# D1-Periph.net
KiCad netlist of a schematic drawn in Altium Designer
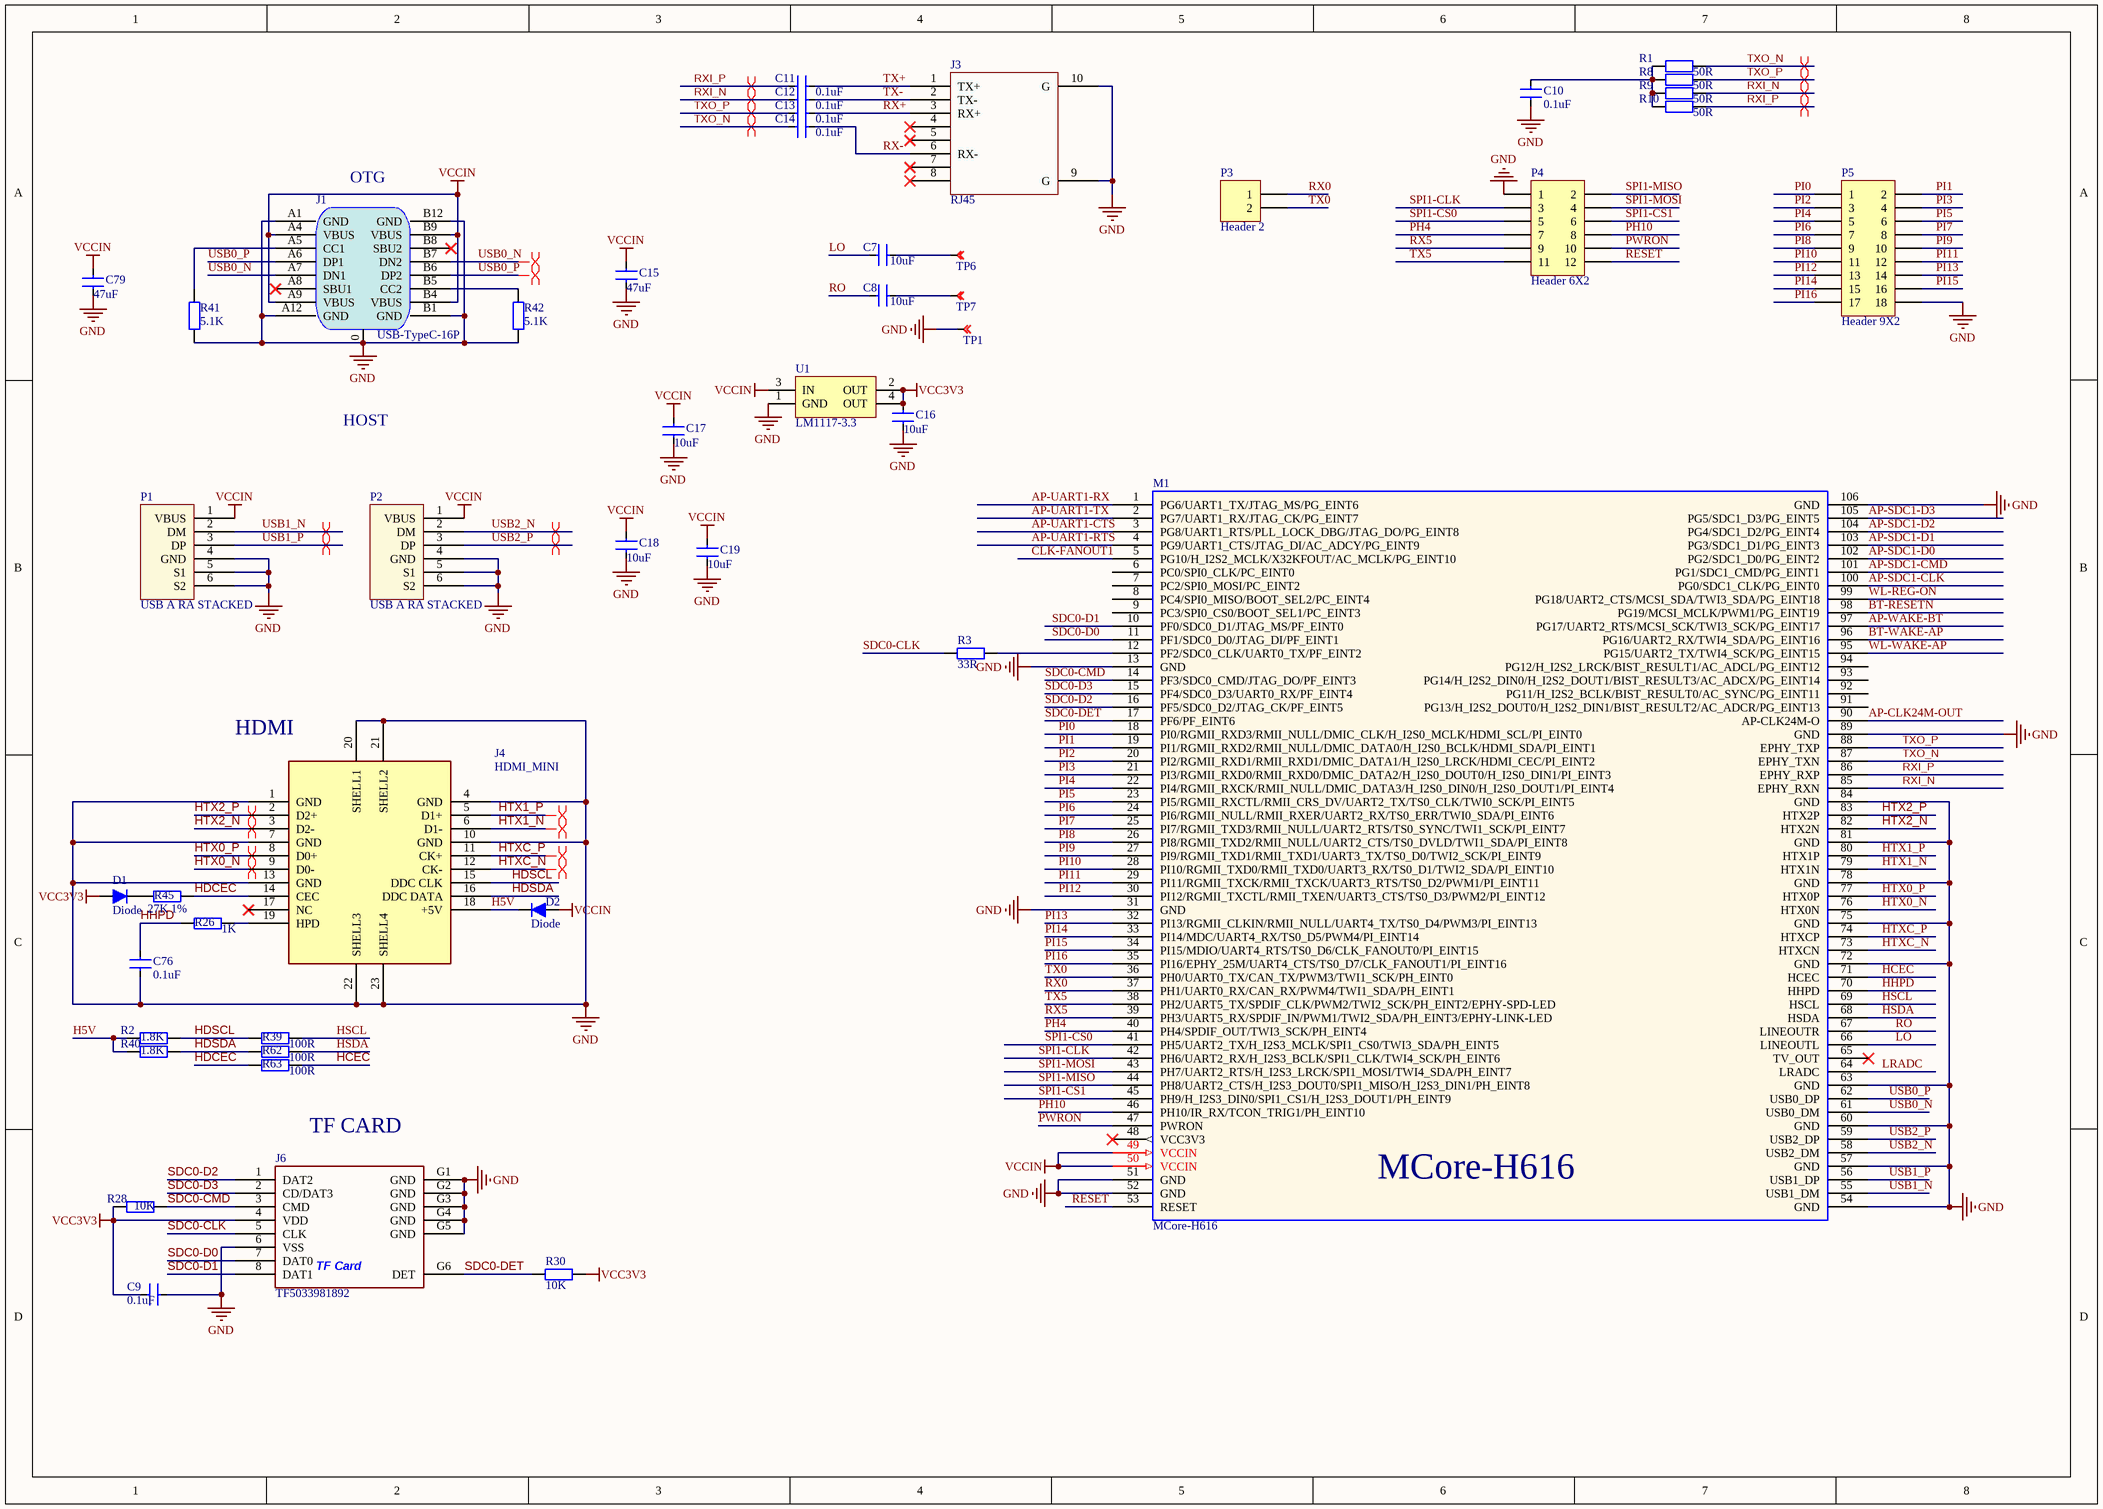
[diagram p0: D1-Periph.SchDoc]

(export (version "E")
  (design (tool "Eeschema 10.0.6"))
  (components
    (comp (ref "C7")
      (value "10uF")
      (footprint "C0402")
      (description "普通小电容")
      (libsource (lib "LIB_MANGO") (part "CAP"))
    )
    (comp (ref "C8")
      (value "10uF")
      (footprint "C0402")
      (description "普通小电容")
      (libsource (lib "LIB_MANGO") (part "CAP"))
    )
    (comp (ref "C9")
      (value "0.1uF")
      (footprint "C0402")
      (description "普通小电容")
      (libsource (lib "LIB_MANGO") (part "CAP"))
    )
    (comp (ref "C10")
      (value "0.1uF")
      (footprint "C0402")
      (description "普通小电容")
      (libsource (lib "LIB_MANGO") (part "CAP"))
    )
    (comp (ref "C11")
      (value "0.1uF")
      (footprint "C0402")
      (description "普通小电容")
      (libsource (lib "LIB_MANGO") (part "CAP"))
    )
    (comp (ref "C12")
      (value "0.1uF")
      (footprint "C0402")
      (description "普通小电容")
      (libsource (lib "LIB_MANGO") (part "CAP"))
    )
    (comp (ref "C13")
      (value "0.1uF")
      (footprint "C0402")
      (description "普通小电容")
      (libsource (lib "LIB_MANGO") (part "CAP"))
    )
    (comp (ref "C14")
      (value "0.1uF")
      (footprint "C0402")
      (description "普通小电容")
      (libsource (lib "LIB_MANGO") (part "CAP"))
    )
    (comp (ref "C15")
      (value "47uF")
      (footprint "C0603")
      (description "普通小电容")
      (libsource (lib "LIB_MANGO") (part "CAP"))
    )
    (comp (ref "C16")
      (value "10uF")
      (footprint "C0402")
      (description "普通小电容")
      (libsource (lib "LIB_MANGO") (part "CAP"))
    )
    (comp (ref "C17")
      (value "10uF")
      (footprint "C0402")
      (description "普通小电容")
      (libsource (lib "LIB_MANGO") (part "CAP"))
    )
    (comp (ref "C18")
      (value "10uF")
      (footprint "C0402")
      (description "普通小电容")
      (libsource (lib "LIB_MANGO") (part "CAP"))
    )
    (comp (ref "C19")
      (value "10uF")
      (footprint "C0402")
      (description "普通小电容")
      (libsource (lib "LIB_MANGO") (part "CAP"))
    )
    (comp (ref "C76")
      (value "0.1uF")
      (footprint "C0402")
      (description "普通小电容")
      (libsource (lib "LIB_MANGO") (part "CAP"))
    )
    (comp (ref "C79")
      (value "47uF")
      (footprint "C0603")
      (description "普通小电容")
      (libsource (lib "LIB_MANGO") (part "CAP"))
    )
    (comp (ref "D1")
      (value "Diode")
      (footprint "SOD523")
      (description "普通二极管")
      (libsource (lib "LIB_MANGO") (part "Diode"))
    )
    (comp (ref "D2")
      (value "Diode")
      (footprint "SOD523")
      (description "普通二极管")
      (libsource (lib "LIB_MANGO") (part "Diode"))
    )
    (comp (ref "J1")
      (value "USB-TypeC-16P")
      (footprint "usb-typec-16p")
      (libsource (lib "LIB_MANGO") (part "USB-TypeC-16P"))
    )
    (comp (ref "J3")
      (value "RJ45")
      (footprint "RJ45")
      (description "RJ45不带网络变压器")
      (libsource (lib "LIB_MANGO") (part "RJ45"))
    )
    (comp (ref "J4")
      (value "HDMI_MINI")
      (footprint "HDMI_T _mini")
      (libsource (lib "LIB_MANGO") (part "HDMI_MINI"))
    )
    (comp (ref "J6")
      (value "TF5033981892")
      (footprint "TFCARD-1040310811")
      (libsource (lib "LIB_MANGO") (part "TF5033981892"))
    )
    (comp (ref "M1")
      (value "MCore-H616")
      (footprint "MCore-H616")
      (libsource (lib "mcore-h616") (part "MCore-H616"))
    )
    (comp (ref "P1")
      (value "USB A RA STACKED")
      (footprint "USB-A STAND")
      (description "CONN RECEPT STACKED USB A RT ANG")
      (libsource (lib "LIB_MANGO") (part "USB A Right Angle Stacked"))
    )
    (comp (ref "P2")
      (value "USB A RA STACKED")
      (footprint "USB-A STAND")
      (description "CONN RECEPT STACKED USB A RT ANG")
      (libsource (lib "LIB_MANGO") (part "USB A Right Angle Stacked"))
    )
    (comp (ref "P3")
      (value "Header 2")
      (footprint "HDR1X2")
      (description "Header, 2-Pin")
      (fields (field (name "PUBLISHER") "Altium Limited"))
      (libsource (lib "LIB_MANGO") (part "Header 2"))
    )
    (comp (ref "P4")
      (value "Header 6X2")
      (footprint "HDR2X6")
      (description "Header, 6-Pin, Dual row")
      (fields (field (name "PUBLISHER") "Altium Limited"))
      (libsource (lib "LIB_MANGO") (part "Header 6X2"))
    )
    (comp (ref "P5")
      (value "Header 9X2")
      (footprint "HDR2X9")
      (description "Header, 9-Pin, Dual row")
      (fields (field (name "PUBLISHER") "Altium Limited"))
      (libsource (lib "LIB_MANGO") (part "Header 9X2"))
    )
    (comp (ref "R1")
      (value "50R")
      (footprint "R0402")
      (description "普通电阻")
      (libsource (lib "LIB_MANGO") (part "RES"))
    )
    (comp (ref "R2")
      (value "1.8K")
      (footprint "R0402")
      (description "普通电阻")
      (libsource (lib "") (part "RES_1"))
    )
    (comp (ref "R3")
      (value "33R")
      (footprint "R0402")
      (description "普通电阻")
      (libsource (lib "") (part "RES_2"))
    )
    (comp (ref "R8")
      (value "50R")
      (footprint "R0402")
      (description "普通电阻")
      (libsource (lib "LIB_MANGO") (part "RES"))
    )
    (comp (ref "R9")
      (value "50R")
      (footprint "R0402")
      (description "普通电阻")
      (libsource (lib "LIB_MANGO") (part "RES"))
    )
    (comp (ref "R10")
      (value "50R")
      (footprint "R0402")
      (description "普通电阻")
      (libsource (lib "LIB_MANGO") (part "RES"))
    )
    (comp (ref "R26")
      (value "1K")
      (footprint "R0402")
      (description "普通电阻")
      (libsource (lib "LIB_MANGO") (part "RES"))
    )
    (comp (ref "R28")
      (value "10K")
      (footprint "R0402")
      (description "普通电阻")
      (libsource (lib "") (part "RES_1"))
    )
    (comp (ref "R30")
      (value "10K")
      (footprint "R0402")
      (description "普通电阻")
      (libsource (lib "") (part "RES_2"))
    )
    (comp (ref "R39")
      (value "100R")
      (footprint "R0402")
      (description "普通电阻")
      (libsource (lib "LIB_MANGO") (part "RES"))
    )
    (comp (ref "R40")
      (value "1.8K")
      (footprint "R0402")
      (description "普通电阻")
      (libsource (lib "") (part "RES_1"))
    )
    (comp (ref "R41")
      (value "5.1K")
      (footprint "R0402")
      (description "普通电阻")
      (libsource (lib "") (part "RES_1"))
    )
    (comp (ref "R42")
      (value "5.1K")
      (footprint "R0402")
      (description "普通电阻")
      (libsource (lib "") (part "RES_1"))
    )
    (comp (ref "R45")
      (value "27K 1%")
      (footprint "R0402")
      (description "普通电阻")
      (libsource (lib "LIB_MANGO") (part "RES"))
    )
    (comp (ref "R62")
      (value "100R")
      (footprint "R0402")
      (description "普通电阻")
      (libsource (lib "LIB_MANGO") (part "RES"))
    )
    (comp (ref "R63")
      (value "100R")
      (footprint "R0402")
      (description "普通电阻")
      (libsource (lib "LIB_MANGO") (part "RES"))
    )
    (comp (ref "TP1")
      (value "TEST POINT")
      (footprint "TEST-POINT1.5")
      (description "Description")
      (libsource (lib "A") (part "TP"))
    )
    (comp (ref "TP6")
      (value "TEST POINT")
      (footprint "TEST-POINT1.5")
      (description "Description")
      (libsource (lib "A") (part "TP"))
    )
    (comp (ref "TP7")
      (value "TEST POINT")
      (footprint "TEST-POINT1.5")
      (description "Description")
      (libsource (lib "A") (part "TP"))
    )
    (comp (ref "U1")
      (value "LM1117-3.3")
      (footprint "SOT223-4N")
      (description "800mA and 1A Low Dropout Positive Regulator 2.85V, 3.3V, 5V, and Adjustable")
      (fields (field (name "PUBLISHER") "Altium Limited"))
      (libsource (lib "LIB_MANGO") (part "LM1117-3.3"))
    )
  )
  (nets
    (net (code "1") (name "/AP-CLK24M-OUT") (class "Default")
      (node (ref "M1") (pin "90") (pinfunction "AP-CLK24M-O_90") (pintype "passive"))
    )
    (net (code "2") (name "/AP-SDC1-CLK") (class "Default")
      (node (ref "M1") (pin "100") (pinfunction "PG0/SDC1_CLK/PG_EINT0_100") (pintype "passive"))
    )
    (net (code "3") (name "/AP-SDC1-CMD") (class "Default")
      (node (ref "M1") (pin "101") (pinfunction "PG1/SDC1_CMD/PG_EINT1_101") (pintype "passive"))
    )
    (net (code "4") (name "/AP-SDC1-D0") (class "Default")
      (node (ref "M1") (pin "102") (pinfunction "PG2/SDC1_D0/PG_EINT2_102") (pintype "passive"))
    )
    (net (code "5") (name "/AP-SDC1-D1") (class "Default")
      (node (ref "M1") (pin "103") (pinfunction "PG3/SDC1_D1/PG_EINT3_103") (pintype "passive"))
    )
    (net (code "6") (name "/AP-SDC1-D2") (class "Default")
      (node (ref "M1") (pin "104") (pinfunction "PG4/SDC1_D2/PG_EINT4_104") (pintype "passive"))
    )
    (net (code "7") (name "/AP-SDC1-D3") (class "Default")
      (node (ref "M1") (pin "105") (pinfunction "PG5/SDC1_D3/PG_EINT5_105") (pintype "passive"))
    )
    (net (code "8") (name "/AP-UART1-CTS") (class "Default")
      (node (ref "M1") (pin "3") (pinfunction "PG8/UART1_RTS/PLL_LOCK_DBG/JTAG_DO/PG_EINT8_3") (pintype "passive"))
    )
    (net (code "9") (name "/AP-UART1-RTS") (class "Default")
      (node (ref "M1") (pin "4") (pinfunction "PG9/UART1_CTS/JTAG_DI/AC_ADCY/PG_EINT9_4") (pintype "passive"))
    )
    (net (code "10") (name "/AP-UART1-RX") (class "Default")
      (node (ref "M1") (pin "1") (pinfunction "PG6/UART1_TX/JTAG_MS/PG_EINT6_1") (pintype "passive"))
    )
    (net (code "11") (name "/AP-UART1-TX") (class "Default")
      (node (ref "M1") (pin "2") (pinfunction "PG7/UART1_RX/JTAG_CK/PG_EINT7_2") (pintype "passive"))
    )
    (net (code "12") (name "/AP-WAKE-BT") (class "Default")
      (node (ref "M1") (pin "97") (pinfunction "PG17/UART2_RTS/MCSI_SCK/TWI3_SCK/PG_EINT17_97") (pintype "passive"))
    )
    (net (code "13") (name "/BT-RESETN") (class "Default")
      (node (ref "M1") (pin "98") (pinfunction "PG19/MCSI_MCLK/PWM1/PG_EINT19_98") (pintype "passive"))
    )
    (net (code "14") (name "/BT-WAKE-AP") (class "Default")
      (node (ref "M1") (pin "96") (pinfunction "PG16/UART2_RX/TWI4_SDA/PG_EINT16_96") (pintype "passive"))
    )
    (net (code "15") (name "/CLK-FANOUT1") (class "Default")
      (node (ref "M1") (pin "5") (pinfunction "PG10/H_I2S2_MCLK/X32KFOUT/AC_MCLK/PG_EINT10_5") (pintype "passive"))
    )
    (net (code "16") (name "/H5V") (class "Default")
      (node (ref "D2") (pin "K") (pinfunction "K_K") (pintype "passive"))
      (node (ref "J4") (pin "18") (pinfunction "+5V_18") (pintype "passive"))
      (node (ref "R2") (pin "1") (pinfunction "1_1") (pintype "passive"))
      (node (ref "R40") (pin "1") (pinfunction "1_1") (pintype "passive"))
    )
    (net (code "17") (name "/HCEC") (class "Default")
      (node (ref "M1") (pin "71") (pinfunction "HCEC_71") (pintype "passive"))
      (node (ref "R63") (pin "1") (pinfunction "1_1") (pintype "passive"))
    )
    (net (code "18") (name "/HDCEC") (class "Default")
      (node (ref "J4") (pin "14") (pinfunction "CEC_14") (pintype "passive"))
      (node (ref "R45") (pin "1") (pinfunction "1_1") (pintype "passive"))
      (node (ref "R63") (pin "2") (pinfunction "2_2") (pintype "passive"))
    )
    (net (code "19") (name "/HDSCL") (class "Default")
      (node (ref "J4") (pin "15") (pinfunction "DDC_CLK_15") (pintype "passive"))
      (node (ref "R2") (pin "2") (pinfunction "2_2") (pintype "passive"))
      (node (ref "R39") (pin "2") (pinfunction "2_2") (pintype "passive"))
    )
    (net (code "20") (name "/HDSDA") (class "Default")
      (node (ref "J4") (pin "16") (pinfunction "DDC_DATA_16") (pintype "passive"))
      (node (ref "R40") (pin "2") (pinfunction "2_2") (pintype "passive"))
      (node (ref "R62") (pin "2") (pinfunction "2_2") (pintype "passive"))
    )
    (net (code "21") (name "/HHPD") (class "Default")
      (node (ref "C76") (pin "2") (pinfunction "2_2") (pintype "passive"))
      (node (ref "M1") (pin "70") (pinfunction "HHPD_70") (pintype "passive"))
      (node (ref "R26") (pin "2") (pinfunction "2_2") (pintype "passive"))
    )
    (net (code "22") (name "/HSCL") (class "Default")
      (node (ref "M1") (pin "69") (pinfunction "HSCL_69") (pintype "passive"))
      (node (ref "R39") (pin "1") (pinfunction "1_1") (pintype "passive"))
    )
    (net (code "23") (name "/HSDA") (class "Default")
      (node (ref "M1") (pin "68") (pinfunction "HSDA_68") (pintype "passive"))
      (node (ref "R62") (pin "1") (pinfunction "1_1") (pintype "passive"))
    )
    (net (code "24") (name "/HTX0_N") (class "Default")
      (node (ref "J4") (pin "9") (pinfunction "D0-_9") (pintype "passive"))
      (node (ref "M1") (pin "76") (pinfunction "HTX0N_76") (pintype "passive"))
    )
    (net (code "25") (name "/HTX0_P") (class "Default")
      (node (ref "J4") (pin "8") (pinfunction "D0+_8") (pintype "passive"))
      (node (ref "M1") (pin "77") (pinfunction "HTX0P_77") (pintype "passive"))
    )
    (net (code "26") (name "/HTX1_N") (class "Default")
      (node (ref "J4") (pin "6") (pinfunction "D1-_6") (pintype "passive"))
      (node (ref "M1") (pin "79") (pinfunction "HTX1N_79") (pintype "passive"))
    )
    (net (code "27") (name "/HTX1_P") (class "Default")
      (node (ref "J4") (pin "5") (pinfunction "D1+_5") (pintype "passive"))
      (node (ref "M1") (pin "80") (pinfunction "HTX1P_80") (pintype "passive"))
    )
    (net (code "28") (name "/HTX2_N") (class "Default")
      (node (ref "J4") (pin "3") (pinfunction "D2-_3") (pintype "passive"))
      (node (ref "M1") (pin "82") (pinfunction "HTX2N_82") (pintype "passive"))
    )
    (net (code "29") (name "/HTX2_P") (class "Default")
      (node (ref "J4") (pin "2") (pinfunction "D2+_2") (pintype "passive"))
      (node (ref "M1") (pin "83") (pinfunction "HTX2P_83") (pintype "passive"))
    )
    (net (code "30") (name "/HTXC_N") (class "Default")
      (node (ref "J4") (pin "12") (pinfunction "CK-_12") (pintype "passive"))
      (node (ref "M1") (pin "73") (pinfunction "HTXCN_73") (pintype "passive"))
    )
    (net (code "31") (name "/HTXC_P") (class "Default")
      (node (ref "J4") (pin "11") (pinfunction "CK+_11") (pintype "passive"))
      (node (ref "M1") (pin "74") (pinfunction "HTXCP_74") (pintype "passive"))
    )
    (net (code "32") (name "/LO") (class "Default")
      (node (ref "C7") (pin "1") (pinfunction "1_1") (pintype "passive"))
      (node (ref "M1") (pin "66") (pinfunction "LINEOUTL_66") (pintype "passive"))
    )
    (net (code "33") (name "/LRADC") (class "Default")
      (node (ref "M1") (pin "64") (pinfunction "LRADC_64") (pintype "passive"))
    )
    (net (code "34") (name "/PH4") (class "Default")
      (node (ref "M1") (pin "40") (pinfunction "PH4/SPDIF_OUT/TWI3_SCK/PH_EINT4_40") (pintype "passive"))
      (node (ref "P4") (pin "7") (pinfunction "7_7") (pintype "passive"))
    )
    (net (code "35") (name "/PH10") (class "Default")
      (node (ref "M1") (pin "46") (pinfunction "PH10/IR_RX/TCON_TRIG1/PH_EINT10_46") (pintype "passive"))
      (node (ref "P4") (pin "8") (pinfunction "8_8") (pintype "passive"))
    )
    (net (code "36") (name "/PI0") (class "Default")
      (node (ref "M1") (pin "18") (pinfunction "PI0/RGMII_RXD3/RMII_NULL/DMIC_CLK/H_I2S0_MCLK/HDMI_SCL/PI_EINT0_18") (pintype "passive"))
      (node (ref "P5") (pin "1") (pinfunction "1_1") (pintype "passive"))
    )
    (net (code "37") (name "/PI1") (class "Default")
      (node (ref "M1") (pin "19") (pinfunction "PI1/RGMII_RXD2/RMII_NULL/DMIC_DATA0/H_I2S0_BCLK/HDMI_SDA/PI_EINT1_19") (pintype "passive"))
      (node (ref "P5") (pin "2") (pinfunction "2_2") (pintype "passive"))
    )
    (net (code "38") (name "/PI2") (class "Default")
      (node (ref "M1") (pin "20") (pinfunction "PI2/RGMII_RXD1/RMII_RXD1/DMIC_DATA1/H_I2S0_LRCK/HDMI_CEC/PI_EINT2_20") (pintype "passive"))
      (node (ref "P5") (pin "3") (pinfunction "3_3") (pintype "passive"))
    )
    (net (code "39") (name "/PI3") (class "Default")
      (node (ref "M1") (pin "21") (pinfunction "PI3/RGMII_RXD0/RMII_RXD0/DMIC_DATA2/H_I2S0_DOUT0/H_I2S0_DIN1/PI_EINT3_21") (pintype "passive"))
      (node (ref "P5") (pin "4") (pinfunction "4_4") (pintype "passive"))
    )
    (net (code "40") (name "/PI4") (class "Default")
      (node (ref "M1") (pin "22") (pinfunction "PI4/RGMII_RXCK/RMII_NULL/DMIC_DATA3/H_I2S0_DIN0/H_I2S0_DOUT1/PI_EINT4_22") (pintype "passive"))
      (node (ref "P5") (pin "5") (pinfunction "5_5") (pintype "passive"))
    )
    (net (code "41") (name "/PI5") (class "Default")
      (node (ref "M1") (pin "23") (pinfunction "PI5/RGMII_RXCTL/RMII_CRS_DV/UART2_TX/TS0_CLK/TWI0_SCK/PI_EINT5_23") (pintype "passive"))
      (node (ref "P5") (pin "6") (pinfunction "6_6") (pintype "passive"))
    )
    (net (code "42") (name "/PI6") (class "Default")
      (node (ref "M1") (pin "24") (pinfunction "PI6/RGMII_NULL/RMII_RXER/UART2_RX/TS0_ERR/TWI0_SDA/PI_EINT6_24") (pintype "passive"))
      (node (ref "P5") (pin "7") (pinfunction "7_7") (pintype "passive"))
    )
    (net (code "43") (name "/PI7") (class "Default")
      (node (ref "M1") (pin "25") (pinfunction "PI7/RGMII_TXD3/RMII_NULL/UART2_RTS/TS0_SYNC/TWI1_SCK/PI_EINT7_25") (pintype "passive"))
      (node (ref "P5") (pin "8") (pinfunction "8_8") (pintype "passive"))
    )
    (net (code "44") (name "/PI8") (class "Default")
      (node (ref "M1") (pin "26") (pinfunction "PI8/RGMII_TXD2/RMII_NULL/UART2_CTS/TS0_DVLD/TWI1_SDA/PI_EINT8_26") (pintype "passive"))
      (node (ref "P5") (pin "9") (pinfunction "9_9") (pintype "passive"))
    )
    (net (code "45") (name "/PI9") (class "Default")
      (node (ref "M1") (pin "27") (pinfunction "PI9/RGMII_TXD1/RMII_TXD1/UART3_TX/TS0_D0/TWI2_SCK/PI_EINT9_27") (pintype "passive"))
      (node (ref "P5") (pin "10") (pinfunction "10_10") (pintype "passive"))
    )
    (net (code "46") (name "/PI10") (class "Default")
      (node (ref "M1") (pin "28") (pinfunction "PI10/RGMII_TXD0/RMII_TXD0/UART3_RX/TS0_D1/TWI2_SDA/PI_EINT10_28") (pintype "passive"))
      (node (ref "P5") (pin "11") (pinfunction "11_11") (pintype "passive"))
    )
    (net (code "47") (name "/PI11") (class "Default")
      (node (ref "M1") (pin "29") (pinfunction "PI11/RGMII_TXCK/RMII_TXCK/UART3_RTS/TS0_D2/PWM1/PI_EINT11_29") (pintype "passive"))
      (node (ref "P5") (pin "12") (pinfunction "12_12") (pintype "passive"))
    )
    (net (code "48") (name "/PI12") (class "Default")
      (node (ref "M1") (pin "30") (pinfunction "PI12/RGMII_TXCTL/RMII_TXEN/UART3_CTS/TS0_D3/PWM2/PI_EINT12_30") (pintype "passive"))
      (node (ref "P5") (pin "13") (pinfunction "13_13") (pintype "passive"))
    )
    (net (code "49") (name "/PI13") (class "Default")
      (node (ref "M1") (pin "32") (pinfunction "PI13/RGMII_CLKIN/RMII_NULL/UART4_TX/TS0_D4/PWM3/PI_EINT13_32") (pintype "passive"))
      (node (ref "P5") (pin "14") (pinfunction "14_14") (pintype "passive"))
    )
    (net (code "50") (name "/PI14") (class "Default")
      (node (ref "M1") (pin "33") (pinfunction "PI14/MDC/UART4_RX/TS0_D5/PWM4/PI_EINT14_33") (pintype "passive"))
      (node (ref "P5") (pin "15") (pinfunction "15_15") (pintype "passive"))
    )
    (net (code "51") (name "/PI15") (class "Default")
      (node (ref "M1") (pin "34") (pinfunction "PI15/MDIO/UART4_RTS/TS0_D6/CLK_FANOUT0/PI_EINT15_34") (pintype "passive"))
      (node (ref "P5") (pin "16") (pinfunction "16_16") (pintype "passive"))
    )
    (net (code "52") (name "/PI16") (class "Default")
      (node (ref "M1") (pin "35") (pinfunction "PI16/EPHY_25M/UART4_CTS/TS0_D7/CLK_FANOUT1/PI_EINT16_35") (pintype "passive"))
      (node (ref "P5") (pin "17") (pinfunction "17_17") (pintype "passive"))
    )
    (net (code "53") (name "/PWRON") (class "Default")
      (node (ref "M1") (pin "47") (pinfunction "PWRON_47") (pintype "passive"))
      (node (ref "P4") (pin "10") (pinfunction "10_10") (pintype "passive"))
    )
    (net (code "54") (name "/RESET") (class "Default")
      (node (ref "M1") (pin "53") (pinfunction "RESET_53") (pintype "passive"))
      (node (ref "P4") (pin "12") (pinfunction "12_12") (pintype "passive"))
    )
    (net (code "55") (name "/RO") (class "Default")
      (node (ref "C8") (pin "1") (pinfunction "1_1") (pintype "passive"))
      (node (ref "M1") (pin "67") (pinfunction "LINEOUTR_67") (pintype "passive"))
    )
    (net (code "56") (name "/RX+") (class "Default")
      (node (ref "C13") (pin "2") (pinfunction "2_2") (pintype "passive"))
      (node (ref "J3") (pin "3") (pinfunction "RX+_3") (pintype "power_in"))
    )
    (net (code "57") (name "/RX-") (class "Default")
      (node (ref "C14") (pin "2") (pinfunction "2_2") (pintype "passive"))
      (node (ref "J3") (pin "6") (pinfunction "RX-_6") (pintype "power_in"))
    )
    (net (code "58") (name "/RX0") (class "Default")
      (node (ref "M1") (pin "37") (pinfunction "PH1/UART0_RX/CAN_RX/PWM4/TWI1_SDA/PH_EINT1_37") (pintype "passive"))
      (node (ref "P3") (pin "1") (pinfunction "1_1") (pintype "passive"))
    )
    (net (code "59") (name "/RX5") (class "Default")
      (node (ref "M1") (pin "39") (pinfunction "PH3/UART5_RX/SPDIF_IN/PWM1/TWI2_SDA/PH_EINT3/EPHY-LINK-LED_39") (pintype "passive"))
      (node (ref "P4") (pin "9") (pinfunction "9_9") (pintype "passive"))
    )
    (net (code "60") (name "/RXI_N") (class "Default")
      (node (ref "C12") (pin "1") (pinfunction "1_1") (pintype "passive"))
      (node (ref "M1") (pin "85") (pinfunction "EPHY_RXN_85") (pintype "passive"))
      (node (ref "R9") (pin "1") (pinfunction "1_1") (pintype "passive"))
    )
    (net (code "61") (name "/RXI_P") (class "Default")
      (node (ref "C11") (pin "1") (pinfunction "1_1") (pintype "passive"))
      (node (ref "M1") (pin "86") (pinfunction "EPHY_RXP_86") (pintype "passive"))
      (node (ref "R10") (pin "1") (pinfunction "1_1") (pintype "passive"))
    )
    (net (code "62") (name "/SDC0-CLK") (class "Default")
      (node (ref "J6") (pin "5") (pinfunction "CLK_5") (pintype "passive"))
      (node (ref "R3") (pin "2") (pinfunction "2_2") (pintype "passive"))
    )
    (net (code "63") (name "/SDC0-CMD") (class "Default")
      (node (ref "J6") (pin "3") (pinfunction "CMD_3") (pintype "passive"))
      (node (ref "M1") (pin "14") (pinfunction "PF3/SDC0_CMD/JTAG_DO/PF_EINT3_14") (pintype "passive"))
      (node (ref "R28") (pin "2") (pinfunction "2_2") (pintype "passive"))
    )
    (net (code "64") (name "/SDC0-D0") (class "Default")
      (node (ref "J6") (pin "7") (pinfunction "DAT0_7") (pintype "passive"))
      (node (ref "M1") (pin "11") (pinfunction "PF1/SDC0_D0/JTAG_DI/PF_EINT1_11") (pintype "passive"))
    )
    (net (code "65") (name "/SDC0-D1") (class "Default")
      (node (ref "J6") (pin "8") (pinfunction "DAT1_8") (pintype "passive"))
      (node (ref "M1") (pin "10") (pinfunction "PF0/SDC0_D1/JTAG_MS/PF_EINT0_10") (pintype "passive"))
    )
    (net (code "66") (name "/SDC0-D2") (class "Default")
      (node (ref "J6") (pin "1") (pinfunction "DAT2_1") (pintype "passive"))
      (node (ref "M1") (pin "16") (pinfunction "PF5/SDC0_D2/JTAG_CK/PF_EINT5_16") (pintype "passive"))
    )
    (net (code "67") (name "/SDC0-D3") (class "Default")
      (node (ref "J6") (pin "2") (pinfunction "CD/DAT3_2") (pintype "passive"))
      (node (ref "M1") (pin "15") (pinfunction "PF4/SDC0_D3/UART0_RX/PF_EINT4_15") (pintype "passive"))
    )
    (net (code "68") (name "/SDC0-DET") (class "Default")
      (node (ref "J6") (pin "G6") (pinfunction "DET_G6") (pintype "power_in"))
      (node (ref "M1") (pin "17") (pinfunction "PF6/PF_EINT6_17") (pintype "passive"))
      (node (ref "R30") (pin "2") (pinfunction "2_2") (pintype "passive"))
    )
    (net (code "69") (name "/SPI1-CLK") (class "Default")
      (node (ref "M1") (pin "42") (pinfunction "PH6/UART2_RX/H_I2S3_BCLK/SPI1_CLK/TWI4_SCK/PH_EINT6_42") (pintype "passive"))
      (node (ref "P4") (pin "3") (pinfunction "3_3") (pintype "passive"))
    )
    (net (code "70") (name "/SPI1-CS0") (class "Default")
      (node (ref "M1") (pin "41") (pinfunction "PH5/UART2_TX/H_I2S3_MCLK/SPI1_CS0/TWI3_SDA/PH_EINT5_41") (pintype "passive"))
      (node (ref "P4") (pin "5") (pinfunction "5_5") (pintype "passive"))
    )
    (net (code "71") (name "/SPI1-CS1") (class "Default")
      (node (ref "M1") (pin "45") (pinfunction "PH9/H_I2S3_DIN0/SPI1_CS1/H_I2S3_DOUT1/PH_EINT9_45") (pintype "passive"))
      (node (ref "P4") (pin "6") (pinfunction "6_6") (pintype "passive"))
    )
    (net (code "72") (name "/SPI1-MISO") (class "Default")
      (node (ref "M1") (pin "44") (pinfunction "PH8/UART2_CTS/H_I2S3_DOUT0/SPI1_MISO/H_I2S3_DIN1/PH_EINT8_44") (pintype "passive"))
      (node (ref "P4") (pin "2") (pinfunction "2_2") (pintype "passive"))
    )
    (net (code "73") (name "/SPI1-MOSI") (class "Default")
      (node (ref "M1") (pin "43") (pinfunction "PH7/UART2_RTS/H_I2S3_LRCK/SPI1_MOSI/TWI4_SDA/PH_EINT7_43") (pintype "passive"))
      (node (ref "P4") (pin "4") (pinfunction "4_4") (pintype "passive"))
    )
    (net (code "74") (name "/TX+") (class "Default")
      (node (ref "C11") (pin "2") (pinfunction "2_2") (pintype "passive"))
      (node (ref "J3") (pin "1") (pinfunction "TX+_1") (pintype "power_in"))
    )
    (net (code "75") (name "/TX-") (class "Default")
      (node (ref "C12") (pin "2") (pinfunction "2_2") (pintype "passive"))
      (node (ref "J3") (pin "2") (pinfunction "TX-_2") (pintype "power_in"))
    )
    (net (code "76") (name "/TX0") (class "Default")
      (node (ref "M1") (pin "36") (pinfunction "PH0/UART0_TX/CAN_TX/PWM3/TWI1_SCK/PH_EINT0_36") (pintype "passive"))
      (node (ref "P3") (pin "2") (pinfunction "2_2") (pintype "passive"))
    )
    (net (code "77") (name "/TX5") (class "Default")
      (node (ref "M1") (pin "38") (pinfunction "PH2/UART5_TX/SPDIF_CLK/PWM2/TWI2_SCK/PH_EINT2/EPHY-SPD-LED_38") (pintype "passive"))
      (node (ref "P4") (pin "11") (pinfunction "11_11") (pintype "passive"))
    )
    (net (code "78") (name "/TXO_N") (class "Default")
      (node (ref "C14") (pin "1") (pinfunction "1_1") (pintype "passive"))
      (node (ref "M1") (pin "87") (pinfunction "EPHY_TXN_87") (pintype "passive"))
      (node (ref "R1") (pin "1") (pinfunction "1_1") (pintype "passive"))
    )
    (net (code "79") (name "/TXO_P") (class "Default")
      (node (ref "C13") (pin "1") (pinfunction "1_1") (pintype "passive"))
      (node (ref "M1") (pin "88") (pinfunction "EPHY_TXP_88") (pintype "passive"))
      (node (ref "R8") (pin "1") (pinfunction "1_1") (pintype "passive"))
    )
    (net (code "80") (name "/USB0_N") (class "Default")
      (node (ref "J1") (pin "A7") (pinfunction "DN1_A7") (pintype "passive"))
      (node (ref "J1") (pin "B7") (pinfunction "DN2_B7") (pintype "passive"))
      (node (ref "M1") (pin "61") (pinfunction "USB0_DM_61") (pintype "passive"))
    )
    (net (code "81") (name "/USB0_P") (class "Default")
      (node (ref "J1") (pin "A6") (pinfunction "DP1_A6") (pintype "passive"))
      (node (ref "J1") (pin "B6") (pinfunction "DP2_B6") (pintype "passive"))
      (node (ref "M1") (pin "62") (pinfunction "USB0_DP_62") (pintype "passive"))
    )
    (net (code "82") (name "/USB1_N") (class "Default")
      (node (ref "M1") (pin "55") (pinfunction "USB1_DM_55") (pintype "passive"))
      (node (ref "P1") (pin "2") (pinfunction "DM_2") (pintype "passive"))
    )
    (net (code "83") (name "/USB1_P") (class "Default")
      (node (ref "M1") (pin "56") (pinfunction "USB1_DP_56") (pintype "passive"))
      (node (ref "P1") (pin "3") (pinfunction "DP_3") (pintype "passive"))
    )
    (net (code "84") (name "/USB2_N") (class "Default")
      (node (ref "M1") (pin "58") (pinfunction "USB2_DM_58") (pintype "passive"))
      (node (ref "P2") (pin "2") (pinfunction "DM_2") (pintype "passive"))
    )
    (net (code "85") (name "/USB2_P") (class "Default")
      (node (ref "M1") (pin "59") (pinfunction "USB2_DP_59") (pintype "passive"))
      (node (ref "P2") (pin "3") (pinfunction "DP_3") (pintype "passive"))
    )
    (net (code "86") (name "/WL-REG-ON") (class "Default")
      (node (ref "M1") (pin "99") (pinfunction "PG18/UART2_CTS/MCSI_SDA/TWI3_SDA/PG_EINT18_99") (pintype "passive"))
    )
    (net (code "87") (name "/WL-WAKE-AP") (class "Default")
      (node (ref "M1") (pin "95") (pinfunction "PG15/UART2_TX/TWI4_SCK/PG_EINT15_95") (pintype "passive"))
    )
    (net (code "88") (name "GND") (class "Default")
      (node (ref "C10") (pin "1") (pinfunction "1_1") (pintype "passive"))
      (node (ref "C15") (pin "2") (pinfunction "2_2") (pintype "passive"))
      (node (ref "C16") (pin "2") (pinfunction "2_2") (pintype "passive"))
      (node (ref "C17") (pin "2") (pinfunction "2_2") (pintype "passive"))
      (node (ref "C18") (pin "2") (pinfunction "2_2") (pintype "passive"))
      (node (ref "C19") (pin "2") (pinfunction "2_2") (pintype "passive"))
      (node (ref "C76") (pin "1") (pinfunction "1_1") (pintype "passive"))
      (node (ref "C79") (pin "2") (pinfunction "2_2") (pintype "passive"))
      (node (ref "C9") (pin "2") (pinfunction "2_2") (pintype "passive"))
      (node (ref "J1") (pin "0") (pinfunction "0_0") (pintype "passive"))
      (node (ref "J1") (pin "A1") (pinfunction "GND_A1") (pintype "passive"))
      (node (ref "J1") (pin "A12") (pinfunction "GND_A12") (pintype "passive"))
      (node (ref "J1") (pin "B1") (pinfunction "GND_B1") (pintype "passive"))
      (node (ref "J1") (pin "B12") (pinfunction "GND_B12") (pintype "passive"))
      (node (ref "J3") (pin "10") (pinfunction "G_10") (pintype "power_in"))
      (node (ref "J3") (pin "9") (pinfunction "G_9") (pintype "power_in"))
      (node (ref "J4") (pin "1") (pinfunction "GND_1") (pintype "passive"))
      (node (ref "J4") (pin "10") (pinfunction "GND_10") (pintype "passive"))
      (node (ref "J4") (pin "13") (pinfunction "GND_13") (pintype "passive"))
      (node (ref "J4") (pin "20") (pinfunction "SHELL1_20") (pintype "passive"))
      (node (ref "J4") (pin "21") (pinfunction "SHELL2_21") (pintype "passive"))
      (node (ref "J4") (pin "22") (pinfunction "SHELL3_22") (pintype "passive"))
      (node (ref "J4") (pin "23") (pinfunction "SHELL4_23") (pintype "passive"))
      (node (ref "J4") (pin "4") (pinfunction "GND_4") (pintype "passive"))
      (node (ref "J4") (pin "7") (pinfunction "GND_7") (pintype "passive"))
      (node (ref "J6") (pin "6") (pinfunction "VSS_6") (pintype "power_in"))
      (node (ref "J6") (pin "G1") (pinfunction "GND_G1") (pintype "power_in"))
      (node (ref "J6") (pin "G2") (pinfunction "GND_G2") (pintype "power_in"))
      (node (ref "J6") (pin "G3") (pinfunction "GND_G3") (pintype "power_in"))
      (node (ref "J6") (pin "G4") (pinfunction "GND_G4") (pintype "power_in"))
      (node (ref "J6") (pin "G5") (pinfunction "GND_G5") (pintype "power_in"))
      (node (ref "M1") (pin "106") (pinfunction "GND_106") (pintype "passive"))
      (node (ref "M1") (pin "13") (pinfunction "GND_13") (pintype "passive"))
      (node (ref "M1") (pin "31") (pinfunction "GND_31") (pintype "passive"))
      (node (ref "M1") (pin "51") (pinfunction "GND_51") (pintype "passive"))
      (node (ref "M1") (pin "52") (pinfunction "GND_52") (pintype "passive"))
      (node (ref "M1") (pin "54") (pinfunction "GND_54") (pintype "passive"))
      (node (ref "M1") (pin "57") (pinfunction "GND_57") (pintype "passive"))
      (node (ref "M1") (pin "60") (pinfunction "GND_60") (pintype "passive"))
      (node (ref "M1") (pin "63") (pinfunction "GND_63") (pintype "passive"))
      (node (ref "M1") (pin "72") (pinfunction "GND_72") (pintype "passive"))
      (node (ref "M1") (pin "75") (pinfunction "GND_75") (pintype "passive"))
      (node (ref "M1") (pin "78") (pinfunction "GND_78") (pintype "passive"))
      (node (ref "M1") (pin "81") (pinfunction "GND_81") (pintype "passive"))
      (node (ref "M1") (pin "84") (pinfunction "GND_84") (pintype "passive"))
      (node (ref "M1") (pin "89") (pinfunction "GND_89") (pintype "passive"))
      (node (ref "P1") (pin "4") (pinfunction "GND_4") (pintype "passive"))
      (node (ref "P1") (pin "5") (pinfunction "S1_5") (pintype "passive"))
      (node (ref "P1") (pin "6") (pinfunction "S2_6") (pintype "passive"))
      (node (ref "P2") (pin "4") (pinfunction "GND_4") (pintype "passive"))
      (node (ref "P2") (pin "5") (pinfunction "S1_5") (pintype "passive"))
      (node (ref "P2") (pin "6") (pinfunction "S2_6") (pintype "passive"))
      (node (ref "P4") (pin "1") (pinfunction "1_1") (pintype "passive"))
      (node (ref "P5") (pin "18") (pinfunction "18_18") (pintype "passive"))
      (node (ref "R41") (pin "1") (pinfunction "1_1") (pintype "passive"))
      (node (ref "R42") (pin "1") (pinfunction "1_1") (pintype "passive"))
      (node (ref "TP1") (pin "1") (pinfunction "1_1") (pintype "passive"))
      (node (ref "U1") (pin "1") (pinfunction "GND_1") (pintype "power_in"))
    )
    (net (code "89") (name "Net-(C7-Pad2)") (class "Default")
      (node (ref "C7") (pin "2") (pinfunction "2_2") (pintype "passive"))
      (node (ref "TP6") (pin "1") (pinfunction "1_1") (pintype "passive"))
    )
    (net (code "90") (name "Net-(C8-Pad2)") (class "Default")
      (node (ref "C8") (pin "2") (pinfunction "2_2") (pintype "passive"))
      (node (ref "TP7") (pin "1") (pinfunction "1_1") (pintype "passive"))
    )
    (net (code "91") (name "Net-(C10-Pad2)") (class "Default")
      (node (ref "C10") (pin "2") (pinfunction "2_2") (pintype "passive"))
      (node (ref "R1") (pin "2") (pinfunction "2_2") (pintype "passive"))
      (node (ref "R10") (pin "2") (pinfunction "2_2") (pintype "passive"))
      (node (ref "R8") (pin "2") (pinfunction "2_2") (pintype "passive"))
      (node (ref "R9") (pin "2") (pinfunction "2_2") (pintype "passive"))
    )
    (net (code "92") (name "Net-(D1-PadK)") (class "Default")
      (node (ref "D1") (pin "K") (pinfunction "K_K") (pintype "passive"))
      (node (ref "R45") (pin "2") (pinfunction "2_2") (pintype "passive"))
    )
    (net (code "93") (name "Net-(J1-CC1)") (class "Default")
      (node (ref "J1") (pin "A5") (pinfunction "CC1_A5") (pintype "passive"))
      (node (ref "R41") (pin "2") (pinfunction "2_2") (pintype "passive"))
    )
    (net (code "94") (name "Net-(J1-CC2)") (class "Default")
      (node (ref "J1") (pin "B5") (pinfunction "CC2_B5") (pintype "passive"))
      (node (ref "R42") (pin "2") (pinfunction "2_2") (pintype "passive"))
    )
    (net (code "95") (name "Net-(J4-HPD)") (class "Default")
      (node (ref "J4") (pin "19") (pinfunction "HPD_19") (pintype "passive"))
      (node (ref "R26") (pin "1") (pinfunction "1_1") (pintype "passive"))
    )
    (net (code "96") (name "Net-(M1-PF2{slash}SDC0_CLK{slash}UART0_TX{slash}PF_EINT2)") (class "Default")
      (node (ref "M1") (pin "12") (pinfunction "PF2/SDC0_CLK/UART0_TX/PF_EINT2_12") (pintype "passive"))
      (node (ref "R3") (pin "1") (pinfunction "1_1") (pintype "passive"))
    )
    (net (code "97") (name "VCC3V3") (class "Default")
      (node (ref "C16") (pin "1") (pinfunction "1_1") (pintype "passive"))
      (node (ref "C9") (pin "1") (pinfunction "1_1") (pintype "passive"))
      (node (ref "D1") (pin "A") (pinfunction "A_A") (pintype "passive"))
      (node (ref "J6") (pin "4") (pinfunction "VDD_4") (pintype "power_in"))
      (node (ref "R28") (pin "1") (pinfunction "1_1") (pintype "passive"))
      (node (ref "R30") (pin "1") (pinfunction "1_1") (pintype "passive"))
      (node (ref "U1") (pin "2") (pinfunction "OUT_2") (pintype "power_in"))
      (node (ref "U1") (pin "4") (pinfunction "OUT_4") (pintype "power_in"))
    )
    (net (code "98") (name "VCCIN") (class "Default")
      (node (ref "C15") (pin "1") (pinfunction "1_1") (pintype "passive"))
      (node (ref "C17") (pin "1") (pinfunction "1_1") (pintype "passive"))
      (node (ref "C18") (pin "1") (pinfunction "1_1") (pintype "passive"))
      (node (ref "C19") (pin "1") (pinfunction "1_1") (pintype "passive"))
      (node (ref "C79") (pin "1") (pinfunction "1_1") (pintype "passive"))
      (node (ref "D2") (pin "A") (pinfunction "A_A") (pintype "passive"))
      (node (ref "J1") (pin "A4") (pinfunction "VBUS_A4") (pintype "passive"))
      (node (ref "J1") (pin "A9") (pinfunction "VBUS_A9") (pintype "passive"))
      (node (ref "J1") (pin "B4") (pinfunction "VBUS_B4") (pintype "passive"))
      (node (ref "J1") (pin "B9") (pinfunction "VBUS_B9") (pintype "passive"))
      (node (ref "M1") (pin "49") (pinfunction "VCCIN_49") (pintype "input"))
      (node (ref "M1") (pin "50") (pinfunction "VCCIN_50") (pintype "input"))
      (node (ref "P1") (pin "1") (pinfunction "VBUS_1") (pintype "passive"))
      (node (ref "P2") (pin "1") (pinfunction "VBUS_1") (pintype "passive"))
      (node (ref "U1") (pin "3") (pinfunction "IN_3") (pintype "power_in"))
    )
    (net (code "99") (name "unconnected-(J1-SBU1-PadA8)") (class "Default")
      (node (ref "J1") (pin "A8") (pinfunction "SBU1_A8") (pintype "passive+no_connect"))
    )
    (net (code "100") (name "unconnected-(J1-SBU2-PadB8)") (class "Default")
      (node (ref "J1") (pin "B8") (pinfunction "SBU2_B8") (pintype "passive+no_connect"))
    )
    (net (code "101") (name "unconnected-(J3-Pad4)") (class "Default")
      (node (ref "J3") (pin "4") (pintype "power_in+no_connect"))
    )
    (net (code "102") (name "unconnected-(J3-Pad5)") (class "Default")
      (node (ref "J3") (pin "5") (pintype "power_in+no_connect"))
    )
    (net (code "103") (name "unconnected-(J3-Pad7)") (class "Default")
      (node (ref "J3") (pin "7") (pintype "power_in+no_connect"))
    )
    (net (code "104") (name "unconnected-(J3-Pad8)") (class "Default")
      (node (ref "J3") (pin "8") (pintype "power_in+no_connect"))
    )
    (net (code "105") (name "unconnected-(J4-NC-Pad17)") (class "Default")
      (node (ref "J4") (pin "17") (pinfunction "NC_17") (pintype "passive+no_connect"))
    )
    (net (code "106") (name "unconnected-(M1-PC0{slash}SPI0_CLK{slash}PC_EINT0-Pad6)") (class "Default")
      (node (ref "M1") (pin "6") (pinfunction "PC0/SPI0_CLK/PC_EINT0_6") (pintype "passive"))
    )
    (net (code "107") (name "unconnected-(M1-PC2{slash}SPI0_MOSI{slash}PC_EINT2-Pad7)") (class "Default")
      (node (ref "M1") (pin "7") (pinfunction "PC2/SPI0_MOSI/PC_EINT2_7") (pintype "passive"))
    )
    (net (code "108") (name "unconnected-(M1-PC3{slash}SPI0_CS0{slash}BOOT_SEL1{slash}PC_EINT3-Pad9)") (class "Default")
      (node (ref "M1") (pin "9") (pinfunction "PC3/SPI0_CS0/BOOT_SEL1/PC_EINT3_9") (pintype "passive"))
    )
    (net (code "109") (name "unconnected-(M1-PC4{slash}SPI0_MISO{slash}BOOT_SEL2{slash}PC_EINT4-Pad8)") (class "Default")
      (node (ref "M1") (pin "8") (pinfunction "PC4/SPI0_MISO/BOOT_SEL2/PC_EINT4_8") (pintype "passive"))
    )
    (net (code "110") (name "unconnected-(M1-PG11{slash}H_I2S2_BCLK{slash}BIST_RESULT0{slash}AC_SYNC{slash}PG_EINT11-Pad92)") (class "Default")
      (node (ref "M1") (pin "92") (pinfunction "PG11/H_I2S2_BCLK/BIST_RESULT0/AC_SYNC/PG_EINT11_92") (pintype "passive"))
    )
    (net (code "111") (name "unconnected-(M1-PG12{slash}H_I2S2_LRCK{slash}BIST_RESULT1{slash}AC_ADCL{slash}PG_EINT12-Pad94)") (class "Default")
      (node (ref "M1") (pin "94") (pinfunction "PG12/H_I2S2_LRCK/BIST_RESULT1/AC_ADCL/PG_EINT12_94") (pintype "passive"))
    )
    (net (code "112") (name "unconnected-(M1-PG13{slash}H_I2S2_DOUT0{slash}H_I2S2_DIN1{slash}BIST_RESULT2{slash}AC_ADCR{slash}PG_EINT13-Pad91)") (class "Default")
      (node (ref "M1") (pin "91") (pinfunction "PG13/H_I2S2_DOUT0/H_I2S2_DIN1/BIST_RESULT2/AC_ADCR/PG_EINT13_91") (pintype "passive"))
    )
    (net (code "113") (name "unconnected-(M1-PG14{slash}H_I2S2_DIN0{slash}H_I2S2_DOUT1{slash}BIST_RESULT3{slash}AC_ADCX{slash}PG_EINT14-Pad93)") (class "Default")
      (node (ref "M1") (pin "93") (pinfunction "PG14/H_I2S2_DIN0/H_I2S2_DOUT1/BIST_RESULT3/AC_ADCX/PG_EINT14_93") (pintype "passive"))
    )
    (net (code "114") (name "unconnected-(M1-TV_OUT-Pad65)") (class "Default")
      (node (ref "M1") (pin "65") (pinfunction "TV_OUT_65") (pintype "passive+no_connect"))
    )
    (net (code "115") (name "unconnected-(M1-VCC3V3-Pad48)") (class "Default")
      (node (ref "M1") (pin "48") (pinfunction "VCC3V3_48") (pintype "output+no_connect"))
    )
  )
)
